# Antenna_Supervisor.net
KiCad netlist of a schematic drawn in Altium Designer
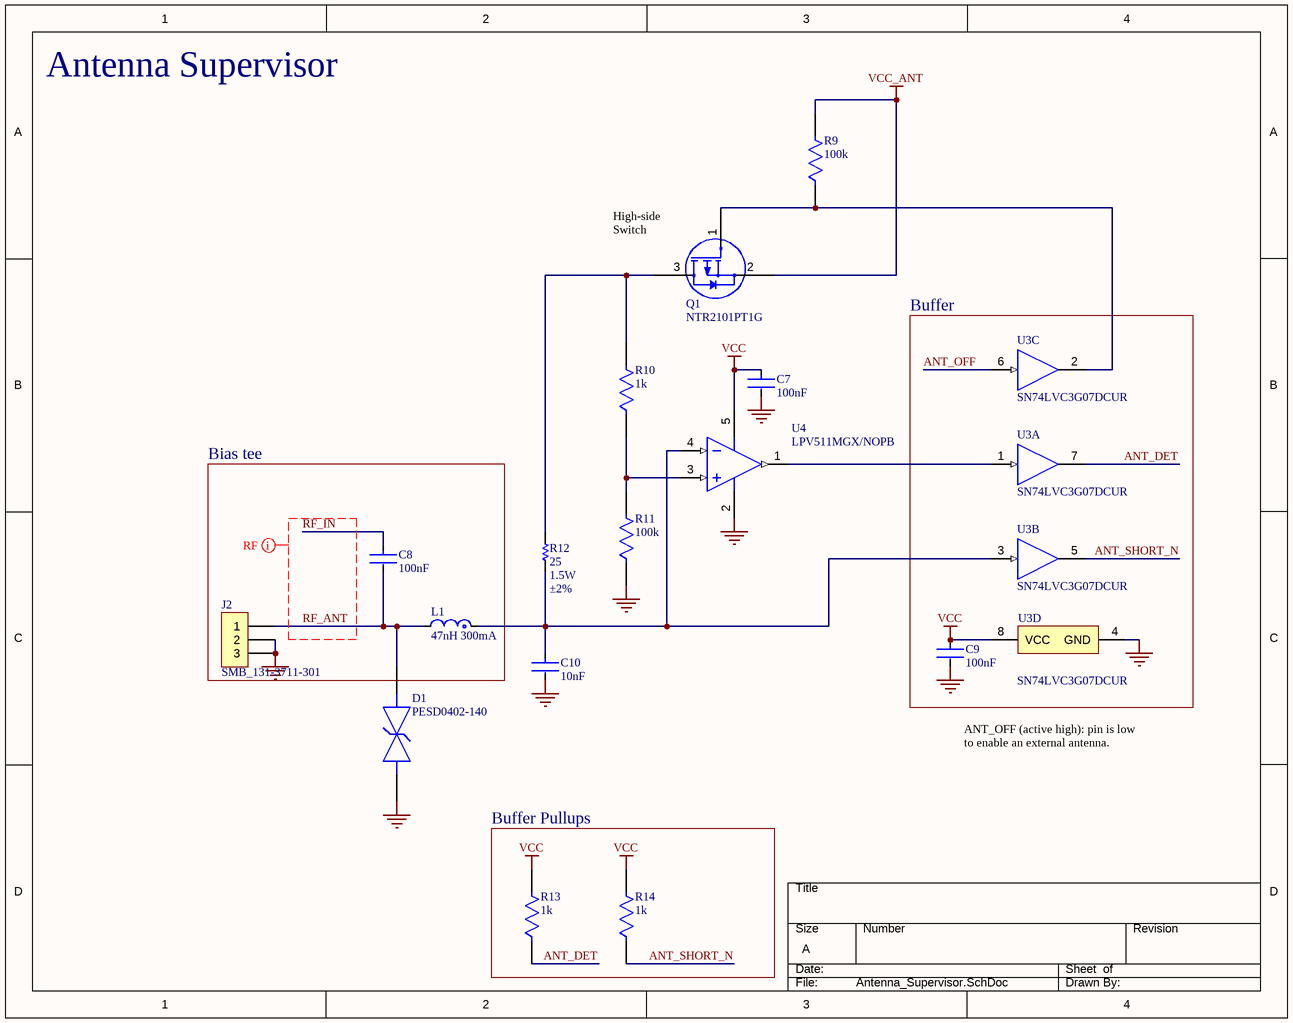
[diagram p0: Antenna_Supervisor.SchDoc]

(export (version "E")
  (design (tool "Eeschema 10.0.6"))
  (components
    (comp (ref "C7")
      (value "100nF")
      (footprint "FP-0402-L_1_0_0_05-W_0_5-IPC_B")
      (description "None")
      (fields (field (name "TOLERANCE") "10%"))
      (libsource (lib "Altium Content Vault") (part "b4654b650e69147ec39a6b967a45e02"))
    )
    (comp (ref "C8")
      (value "100nF")
      (footprint "FP-0402-L_1_0_0_05-W_0_5-IPC_B")
      (description "None")
      (fields (field (name "TOLERANCE") "10%"))
      (libsource (lib "Altium Content Vault") (part "b4654b650e69147ec39a6b967a45e02"))
    )
    (comp (ref "C9")
      (value "100nF")
      (footprint "FP-0402-L_1_0_0_05-W_0_5-IPC_B")
      (description "None")
      (fields (field (name "TOLERANCE") "10%"))
      (libsource (lib "Altium Content Vault") (part "b4654b650e69147ec39a6b967a45e02"))
    )
    (comp (ref "C10")
      (value "10nF")
      (footprint "FP-GRM033-0_03-IPC_B")
      (description "Chip Multilayer Ceramic Capacitors for General Purpose, 0201, 10000pF, X7R, 15%, 10%, 16V")
      (fields (field (name "TOLERANCE") "10%"))
      (libsource (lib "Altium Content Vault") (part "b4654b650e69147ec39a6b967a45e02"))
    )
    (comp (ref "D1")
      (value "PESD0402-140")
      (footprint "FP-PESD0402-MFG")
      (description "TVS DIODE 14V 40V 0402")
      (fields
        (field (name "OCTOPART") "https://octopart.com/pesd0402-140-littelfuse-74215061")
        (field (name "MANUFACTURER") "Littelfuse Inc.")
      )
      (libsource (lib "Altium Content Vault") (part "edccc070dd5cba1f9372128faf3915e"))
    )
    (comp (ref "J2")
      (value "SMB_131-3711-301")
      (footprint "CONN_131-3711-301")
      (description "Rf Coaxial Board Mount Connector")
      (fields
        (field (name "MANUFACTURER") "Bel Cinch")
        (field (name "MANUFACTURER PART NUMBER") "131-3711-301")
      )
      (libsource (lib "MyLibrary") (part "CONN_131-3711-301"))
    )
    (comp (ref "L1")
      (value "47nH 300mA")
      (footprint "FP-LQG15HH_02-IPC_B")
      (description "Multilayer type RF Inductor 47nH ±5% 0.72Ω 300mA 0402")
      (fields (field (name "TOLERANCE") "5%"))
      (libsource (lib "Altium Content Vault") (part "4cc4b267dca4c8e51f7102f422741d8"))
    )
    (comp (ref "Q1")
      (value "onsemi_NTR2101PT1G")
      (footprint "SOT23_3pins_300x140x112")
      (description "MOSFET, P-CH, 8VDS, 3.7A ID, 0.052 OHM RDS(ON)@4.5VGS/3.5A, SOT-23-3")
      (fields
        (field (name "MANUFACTURER") "onsemi")
        (field (name "MANUFACTURER PART NUMBER") "NTR2101PT1G")
        (field (name "INTERNAL PART NUMBER") "839-00735-00")
      )
      (libsource (lib "RL Research Altium Server") (part "Transistor_MOS-P-CH_3pins_1G_1S_1D_DIO"))
    )
    (comp (ref "R9")
      (value "100k")
      (footprint "FP-RMCF0402-IPC_C")
      (description "100kΩ ±1% 0.063W 0402 Thick Film Chip Resistor AEC-Q200 compliant")
      (fields (field (name "TOLERANCE") "1%"))
      (libsource (lib "Altium Content Vault") (part "1029c3af85768c4190bb7ad29bc67b5"))
    )
    (comp (ref "R10")
      (value "1k")
      (footprint "FP-RMCF0402-MFG")
      (description "1kΩ ±1% 0.063W 0402 Thick Film Chip Resistor AEC-Q200 compliant")
      (fields (field (name "TOLERANCE") "1%"))
      (libsource (lib "Altium Content Vault") (part "1029c3af85768c4190bb7ad29bc67b5"))
    )
    (comp (ref "R11")
      (value "100k")
      (footprint "FP-RMCF0402-IPC_C")
      (description "100kΩ ±1% 0.063W 0402 Thick Film Chip Resistor AEC-Q200 compliant")
      (fields (field (name "TOLERANCE") "1%"))
      (libsource (lib "Altium Content Vault") (part "1029c3af85768c4190bb7ad29bc67b5"))
    )
    (comp (ref "R12")
      (value "Vishay_RCP0603W25R0GEB")
      (footprint "RESC1608X055N")
      (description "RES, 25 OHM, 2%, 1.5W, 150PPM/C, 0603")
      (fields
        (field (name "RESISTANCE") "25")
        (field (name "POWER (WATTS)") "1.5W")
        (field (name "TOLERANCE") "±2%")
        (field (name "INTERNAL PART NUMBER") "822-00198-00")
        (field (name "MANUFACTURER") "Vishay")
      )
      (libsource (lib "RL Research Altium Server") (part "Resistor_300mil"))
    )
    (comp (ref "R13")
      (value "1k")
      (footprint "FP-RMCF0402-MFG")
      (description "1kΩ ±1% 0.063W 0402 Thick Film Chip Resistor AEC-Q200 compliant")
      (fields (field (name "TOLERANCE") "1%"))
      (libsource (lib "Altium Content Vault") (part "1029c3af85768c4190bb7ad29bc67b5"))
    )
    (comp (ref "R14")
      (value "1k")
      (footprint "FP-RMCF0402-MFG")
      (description "1kΩ ±1% 0.063W 0402 Thick Film Chip Resistor AEC-Q200 compliant")
      (fields (field (name "TOLERANCE") "1%"))
      (libsource (lib "Altium Content Vault") (part "1029c3af85768c4190bb7ad29bc67b5"))
    )
    (comp (ref "U3")
      (value "SN74LVC3G07DCUR")
      (footprint "DCU0008A_N")
      (description "Triple Buffer/Driver With Open-Drain Output, DCU0008A, LARGE T&R")
      (fields
        (field (name "GENERIC PART NUMBER") "SN74LVC3G07")
        (field (name "MANUFACTURER") "Texas Instruments")
      )
      (libsource (lib "Altium Content Vault") (part "TI-SN74XXX3G0X-XX-8"))
    )
    (comp (ref "U4")
      (value "LPV511MGX/NOPB")
      (footprint "DCK0005A_N")
      (description "micropower Rail-to-Rail Input and Output Operational Amplifier, 5-pin SC-70, Pb-Free")
      (fields (field (name "MANUFACTURER") "Texas Instruments"))
      (libsource (lib "Altium Content Vault") (part "AMP-OPA-LM7121-5"))
    )
  )
  (nets
    (net (code "1") (name "/ANT_DET") (class "Default")
      (node (ref "R13") (pin "1") (pinfunction "1_1") (pintype "passive"))
      (node (ref "U3") (pin "7") (pinfunction "1Y_7") (pintype "open_collector"))
    )
    (net (code "2") (name "/ANT_OFF") (class "Default")
      (node (ref "U3") (pin "6") (pinfunction "3A_6") (pintype "input"))
    )
    (net (code "3") (name "/ANT_SHORT_N") (class "Default")
      (node (ref "R14") (pin "1") (pinfunction "1_1") (pintype "passive"))
      (node (ref "U3") (pin "5") (pinfunction "2Y_5") (pintype "open_collector"))
    )
    (net (code "4") (name "/RF_ANT") (class "Default")
      (node (ref "C8") (pin "2") (pinfunction "2_2") (pintype "passive"))
      (node (ref "D1") (pin "2") (pinfunction "2_2") (pintype "passive"))
      (node (ref "J2") (pin "1") (pinfunction "1_1") (pintype "passive"))
      (node (ref "L1") (pin "2") (pinfunction "2_2") (pintype "passive"))
    )
    (net (code "5") (name "/RF_IN") (class "Default")
      (node (ref "C8") (pin "1") (pinfunction "1_1") (pintype "passive"))
    )
    (net (code "6") (name "GND") (class "Default")
      (node (ref "C10") (pin "2") (pinfunction "2_2") (pintype "passive"))
      (node (ref "C7") (pin "2") (pinfunction "2_2") (pintype "passive"))
      (node (ref "C9") (pin "2") (pinfunction "2_2") (pintype "passive"))
      (node (ref "D1") (pin "1") (pinfunction "1_1") (pintype "passive"))
      (node (ref "J2") (pin "2") (pinfunction "2_2") (pintype "passive"))
      (node (ref "J2") (pin "3") (pinfunction "3_3") (pintype "passive"))
      (node (ref "R11") (pin "1") (pinfunction "1_1") (pintype "passive"))
      (node (ref "U3") (pin "4") (pinfunction "GND_4") (pintype "power_in"))
      (node (ref "U4") (pin "2") (pinfunction "V-_2") (pintype "power_in"))
    )
    (net (code "7") (name "Net-(Q1-D)") (class "Default")
      (node (ref "Q1") (pin "3") (pinfunction "D_3") (pintype "passive"))
      (node (ref "R10") (pin "2") (pinfunction "2_2") (pintype "passive"))
      (node (ref "R12") (pin "1") (pinfunction "1_1") (pintype "passive"))
    )
    (net (code "8") (name "Net-(Q1-G)") (class "Default")
      (node (ref "Q1") (pin "1") (pinfunction "G_1") (pintype "passive"))
      (node (ref "R9") (pin "1") (pinfunction "1_1") (pintype "passive"))
      (node (ref "U3") (pin "2") (pinfunction "3Y_2") (pintype "open_collector"))
    )
    (net (code "9") (name "Net-(U3A-1A)") (class "Default")
      (node (ref "U3") (pin "1") (pinfunction "1A_1") (pintype "input"))
      (node (ref "U4") (pin "1") (pinfunction "OUT_1") (pintype "output"))
    )
    (net (code "10") (name "Net-(U3B-2A)") (class "Default")
      (node (ref "C10") (pin "1") (pinfunction "1_1") (pintype "passive"))
      (node (ref "L1") (pin "1") (pinfunction "1_1") (pintype "passive"))
      (node (ref "R12") (pin "2") (pinfunction "2_2") (pintype "passive"))
      (node (ref "U3") (pin "3") (pinfunction "2A_3") (pintype "input"))
      (node (ref "U4") (pin "4") (pinfunction "IN-_4") (pintype "input"))
    )
    (net (code "11") (name "Net-(U4-IN+)") (class "Default")
      (node (ref "R10") (pin "1") (pinfunction "1_1") (pintype "passive"))
      (node (ref "R11") (pin "2") (pinfunction "2_2") (pintype "passive"))
      (node (ref "U4") (pin "3") (pinfunction "IN+_3") (pintype "input"))
    )
    (net (code "12") (name "VCC") (class "Default")
      (node (ref "C7") (pin "1") (pinfunction "1_1") (pintype "passive"))
      (node (ref "C9") (pin "1") (pinfunction "1_1") (pintype "passive"))
      (node (ref "R13") (pin "2") (pinfunction "2_2") (pintype "passive"))
      (node (ref "R14") (pin "2") (pinfunction "2_2") (pintype "passive"))
      (node (ref "U3") (pin "8") (pinfunction "VCC_8") (pintype "power_in"))
      (node (ref "U4") (pin "5") (pinfunction "V+_5") (pintype "power_in"))
    )
    (net (code "13") (name "VCC_ANT") (class "Default")
      (node (ref "Q1") (pin "2") (pinfunction "S_2") (pintype "passive"))
      (node (ref "R9") (pin "2") (pinfunction "2_2") (pintype "passive"))
    )
  )
)
